# optosch.net
KiCad netlist of a schematic drawn in EAGLE
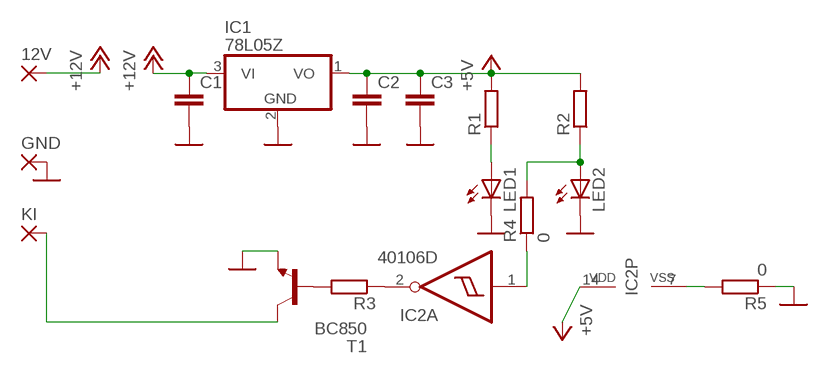
[diagram p0: schematic, sheet 1]

(export (version "E")
  (design (tool "Eeschema 10.0.6"))
  (components
    (comp (ref "12V")
      (value "2,15/1,0")
      (footprint "eagle-import:2,15_1,0")
      (libsource (lib "eagle-import") (part "2,15/1,0"))
    )
    (comp (ref "C1")
      (value "C-EUC3216")
      (footprint "eagle-import:C3216")
      (libsource (lib "eagle-import") (part "C-EUC3216"))
    )
    (comp (ref "C2")
      (value "C-EUC3216")
      (footprint "eagle-import:C3216")
      (libsource (lib "eagle-import") (part "C-EUC3216"))
    )
    (comp (ref "C3")
      (value "C-EUC3216")
      (footprint "eagle-import:C3216")
      (libsource (lib "eagle-import") (part "C-EUC3216"))
    )
    (comp (ref "GND")
      (value "2,15/1,0")
      (footprint "eagle-import:2,15_1,0")
      (libsource (lib "eagle-import") (part "2,15/1,0"))
    )
    (comp (ref "IC1")
      (value "78L05Z")
      (footprint "eagle-import:TO92")
      (libsource (lib "eagle-import") (part "78ZL05"))
    )
    (comp (ref "IC2")
      (value "40106D")
      (footprint "eagle-import:SO14")
      (libsource (lib "eagle-import") (part "40106D"))
    )
    (comp (ref "KI")
      (value "2,15/1,0")
      (footprint "eagle-import:2,15_1,0")
      (libsource (lib "eagle-import") (part "2,15/1,0"))
    )
    (comp (ref "LED1")
      (value "LED5MM")
      (footprint "eagle-import:LED5MM")
      (libsource (lib "eagle-import") (part "LED5MM"))
    )
    (comp (ref "LED2")
      (value "LED5MM")
      (footprint "eagle-import:LED5MM")
      (libsource (lib "eagle-import") (part "LED5MM"))
    )
    (comp (ref "R1")
      (value "R-EU_M1206")
      (footprint "eagle-import:M1206")
      (libsource (lib "eagle-import") (part "R-EU_M1206"))
    )
    (comp (ref "R2")
      (value "R-EU_M1206")
      (footprint "eagle-import:M1206")
      (libsource (lib "eagle-import") (part "R-EU_M1206"))
    )
    (comp (ref "R3")
      (value "R-EU_M1206")
      (footprint "eagle-import:M1206")
      (libsource (lib "eagle-import") (part "R-EU_M1206"))
    )
    (comp (ref "R4")
      (value "0")
      (footprint "eagle-import:M1206")
      (libsource (lib "eagle-import") (part "R-EU_M1206"))
    )
    (comp (ref "R5")
      (value "0")
      (footprint "eagle-import:M1206")
      (libsource (lib "eagle-import") (part "R-EU_M1206"))
    )
    (comp (ref "T1")
      (value "BC850")
      (footprint "eagle-import:SOT23")
      (libsource (lib "eagle-import") (part "BC850"))
    )
  )
  (nets
    (net (code "1") (name "+5V") (class "Default")
      (node (ref "C2") (pin "1") (pinfunction "1_1") (pintype "passive"))
      (node (ref "C3") (pin "1") (pinfunction "1_1") (pintype "passive"))
      (node (ref "IC1") (pin "1") (pinfunction "VO_1") (pintype "passive"))
      (node (ref "IC2") (pin "14") (pinfunction "VDD_14") (pintype "power_in"))
      (node (ref "R1") (pin "2") (pinfunction "2_2") (pintype "passive"))
      (node (ref "R2") (pin "2") (pinfunction "2_2") (pintype "passive"))
    )
    (net (code "2") (name "+12V") (class "Default")
      (node (ref "12V") (pin "1") (pinfunction "P_1") (pintype "passive"))
      (node (ref "C1") (pin "1") (pinfunction "1_1") (pintype "passive"))
      (node (ref "IC1") (pin "3") (pinfunction "VI_3") (pintype "input"))
    )
    (net (code "3") (name "/N$1") (class "Default")
      (node (ref "IC2") (pin "1") (pinfunction "I_1") (pintype "input"))
      (node (ref "LED2") (pin "A") (pinfunction "A_A") (pintype "passive"))
      (node (ref "R2") (pin "1") (pinfunction "1_1") (pintype "passive"))
      (node (ref "R4") (pin "1") (pinfunction "1_1") (pintype "passive"))
      (node (ref "R4") (pin "2") (pinfunction "2_2") (pintype "passive"))
    )
    (net (code "4") (name "GND") (class "Default")
      (node (ref "C1") (pin "2") (pinfunction "2_2") (pintype "passive"))
      (node (ref "C2") (pin "2") (pinfunction "2_2") (pintype "passive"))
      (node (ref "C3") (pin "2") (pinfunction "2_2") (pintype "passive"))
      (node (ref "GND") (pin "1") (pinfunction "P_1") (pintype "passive"))
      (node (ref "IC1") (pin "2") (pinfunction "GND_2") (pintype "passive"))
      (node (ref "IC2") (pin "7") (pinfunction "VSS_7") (pintype "power_in"))
      (node (ref "LED1") (pin "K") (pinfunction "C_K") (pintype "passive"))
      (node (ref "LED2") (pin "K") (pinfunction "C_K") (pintype "passive"))
      (node (ref "R5") (pin "1") (pinfunction "1_1") (pintype "passive"))
      (node (ref "R5") (pin "2") (pinfunction "2_2") (pintype "passive"))
      (node (ref "T1") (pin "2") (pinfunction "E_2") (pintype "passive"))
    )
    (net (code "5") (name "Net-(IC2A-O)") (class "Default")
      (node (ref "IC2") (pin "2") (pinfunction "O_2") (pintype "output"))
      (node (ref "R3") (pin "1") (pinfunction "1_1") (pintype "passive"))
    )
    (net (code "6") (name "Net-(KI-P)") (class "Default")
      (node (ref "KI") (pin "1") (pinfunction "P_1") (pintype "passive"))
      (node (ref "T1") (pin "3") (pinfunction "C_3") (pintype "passive"))
    )
    (net (code "7") (name "Net-(LED1-PadA)") (class "Default")
      (node (ref "LED1") (pin "A") (pinfunction "A_A") (pintype "passive"))
      (node (ref "R1") (pin "1") (pinfunction "1_1") (pintype "passive"))
    )
    (net (code "8") (name "Net-(T1-B)") (class "Default")
      (node (ref "R3") (pin "2") (pinfunction "2_2") (pintype "passive"))
      (node (ref "T1") (pin "1") (pinfunction "B_1") (pintype "passive"))
    )
  )
)
